# Solar_Charger_Schematic.net
KiCad netlist of a schematic drawn in Altium Designer
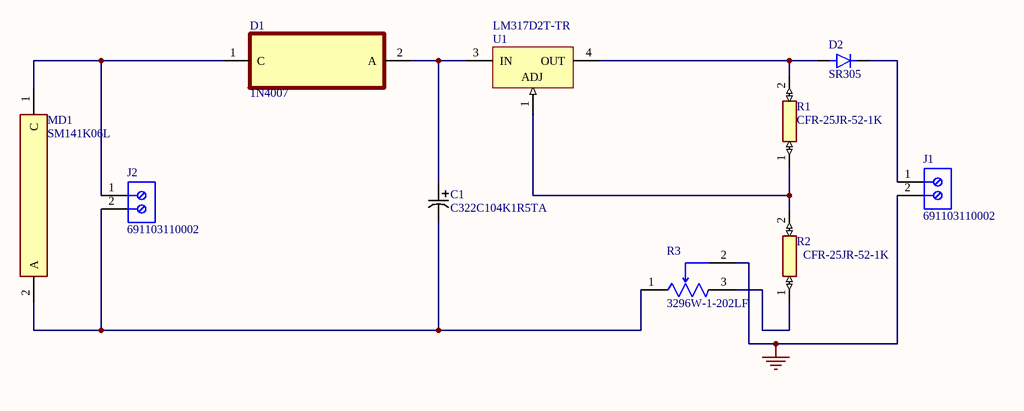
[diagram p0: Solar_Charger_Schematic.SchDoc]

(export (version "E")
  (design (tool "Eeschema 10.0.6"))
  (components
    (comp (ref "C1")
      (value "C322C104K1R5TA")
      (footprint "CAP_C322_KEM")
      (description "No Description Available")
      (fields (field (name "COPYRIGHT") "Copyright (C) 2023 Ultra Librarian. All rights reserved."))
      (libsource (lib "Solar_Charger_SCHLIB") (part "C322C104K1R5TA"))
    )
    (comp (ref "D1")
      (value "1N4007")
      (footprint "DIO_1N5282")
      (description "Diode 1000 V 1A Through Hole DO-41")
      (fields (field (name "MF") "ON") (field (name "MP") "1N5282"))
      (libsource (lib "Solar_Charger_SCHLIB") (part "1N4007"))
    )
    (comp (ref "D2")
      (value "SR305")
      (footprint "DIOAD1990W125L900D530")
      (description "3A, 50V, Schottky Rectifier")
      (fields (field (name "MF") "Taiwan Semiconductor"))
      (libsource (lib "Solar_Charger_SCHLIB") (part "SR305"))
    )
    (comp (ref "J1")
      (value "691103110002")
      (footprint "691103110002")
      (fields (field (name "VOLTAGE") "125V"))
      (libsource (lib "Solar_Charger_SCHLIB") (part "Terminal_Block"))
    )
    (comp (ref "J2")
      (value "691103110002")
      (footprint "691103110002")
      (fields (field (name "VOLTAGE") "125V"))
      (libsource (lib "Solar_Charger_SCHLIB") (part "Terminal_Block"))
    )
    (comp (ref "MD1")
      (value "SM141K06L")
      (footprint "FP-SM141K06L-MFG")
      (description "MONOCRYST SOLAR CELL 184MW 4.15V")
      (libsource (lib "Solar_Charger_SCHLIB") (part "CMP-48341-000002-1"))
    )
    (comp (ref "R1")
      (value "CFR-25JR-52-1K")
      (footprint "RESAD1590W60L630D240")
      (description "1.1 kOhms Â±5% 0.25W, 1/4W Through Hole Resistor Axial - Carbon Film")
      (fields (field (name "MF") "Yageo"))
      (libsource (lib "Solar_Charger_SCHLIB") (part "CFR-25JR-52-1K"))
    )
    (comp (ref "R2")
      (value "CFR-25JR-52-1K")
      (footprint "RESAD1590W60L630D240")
      (description "1.1 kOhms Â±5% 0.25W, 1/4W Through Hole Resistor Axial - Carbon Film")
      (fields (field (name "MF") "Yageo"))
      (libsource (lib "Solar_Charger_SCHLIB") (part "CFR-25JR-52-1K"))
    )
    (comp (ref "R3")
      (value "3296W-1-202LF")
      (footprint "FP-3296W-MFG")
      (description "TRIMMER 2K OHM 0.5W PC PIN TOP")
      (fields (field (name "TOLERANCE") "10%"))
      (libsource (lib "Solar_Charger_SCHLIB") (part "CMP-2000-05582-2"))
    )
    (comp (ref "U1")
      (value "LM317D2T-TR")
      (footprint "TO-263_N")
      (description "1.5A, 1.2V to 37V Adjustable Voltage Regulator, 3-Pin D2PAK, Tape and Reel")
      (libsource (lib "Solar_Charger_SCHLIB") (part "CMP-0244-00094-1"))
    )
  )
  (nets
    (net (code "1") (name "GND") (class "Default")
      (node (ref "J1") (pin "2") (pinfunction "2_2") (pintype "passive"))
      (node (ref "R3") (pin "2") (pinfunction "WIPER_2") (pintype "passive"))
    )
    (net (code "2") (name "Net-(D1-A)") (class "Default")
      (node (ref "C1") (pin "1") (pinfunction "1_1") (pintype "passive"))
      (node (ref "D1") (pin "2") (pinfunction "A_2") (pintype "passive"))
      (node (ref "U1") (pin "3") (pinfunction "IN_3") (pintype "power_in"))
    )
    (net (code "3") (name "Net-(D1-C)") (class "Default")
      (node (ref "D1") (pin "1") (pinfunction "C_1") (pintype "passive"))
      (node (ref "J2") (pin "1") (pinfunction "1_1") (pintype "passive"))
      (node (ref "MD1") (pin "1") (pinfunction "C_1") (pintype "passive"))
    )
    (net (code "4") (name "Net-(D2-K)") (class "Default")
      (node (ref "D2") (pin "C") (pinfunction "K_C") (pintype "passive"))
      (node (ref "J1") (pin "1") (pinfunction "1_1") (pintype "passive"))
    )
    (net (code "5") (name "Net-(MD1-A)") (class "Default")
      (node (ref "C1") (pin "2") (pinfunction "2_2") (pintype "passive"))
      (node (ref "J2") (pin "2") (pinfunction "2_2") (pintype "passive"))
      (node (ref "MD1") (pin "2") (pinfunction "A_2") (pintype "passive"))
      (node (ref "R3") (pin "1") (pinfunction "CCW_1") (pintype "passive"))
    )
    (net (code "6") (name "Net-(R3-CW)") (class "Default")
      (node (ref "R2") (pin "1") (pinfunction "1_1") (pintype "bidirectional"))
      (node (ref "R3") (pin "3") (pinfunction "CW_3") (pintype "passive"))
    )
    (net (code "7") (name "Net-(U1-ADJ)") (class "Default")
      (node (ref "R1") (pin "1") (pinfunction "1_1") (pintype "bidirectional"))
      (node (ref "R2") (pin "2") (pinfunction "2_2") (pintype "bidirectional"))
      (node (ref "U1") (pin "1") (pinfunction "ADJ_1") (pintype "input"))
    )
    (net (code "8") (name "Net-(U1-OUT)") (class "Default")
      (node (ref "D2") (pin "A") (pinfunction "A_A") (pintype "passive"))
      (node (ref "R1") (pin "2") (pinfunction "2_2") (pintype "bidirectional"))
      (node (ref "U1") (pin "4") (pinfunction "OUT_4") (pintype "power_in"))
    )
  )
)
